# PUMP.net
KiCad netlist of a schematic drawn in Altium Designer
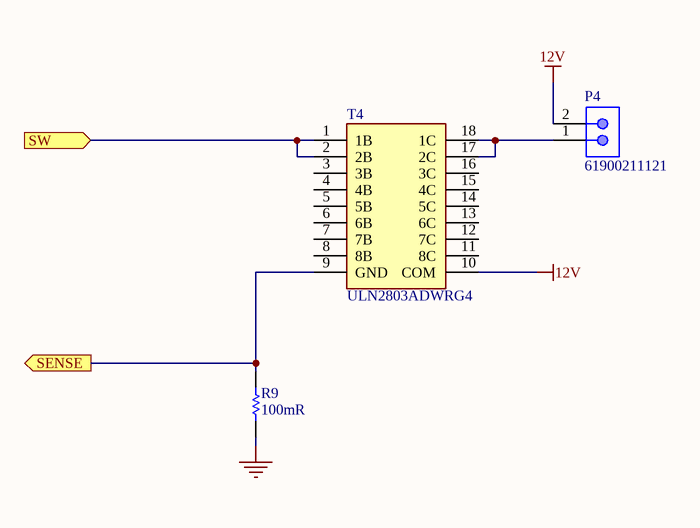
[diagram p0: PUMP.SchDoc]

(export (version "E")
  (design (tool "Eeschema 10.0.6"))
  (components
    (comp (ref "P4")
      (value "61900211121")
      (footprint "61900211121")
      (description "WR-WTB THT Male Vertical Locking Header, pitch 2.54mm, 2p")
      (fields (field (name "PUBLISHER") "Wurth Elektronik"))
      (libsource (lib "Altium_WR-WTB (rev20a)") (part "61900211121"))
    )
    (comp (ref "R9")
      (value "100mR")
      (footprint "RES_1206_H060 (_IPC_MD)")
      (description "100mR 1% 0,25W 200V 1206")
      (fields (field (name "PART NUMBER") "RES100mR1%1206"))
      (libsource (lib "MUAB_Altium_Lib") (part "RES"))
    )
    (comp (ref "T4")
      (value "ULN2803ADWRG4")
      (footprint "OpenBrewie:SOIC127P1030X265-18N")
      (description "Darlington")
      (fields (field (name "MOUSER PART NUMBER") "595-ULN2803ADWRG4"))
      (libsource (lib "OpenBrewie") (part "ULN2803ADWRG4"))
    )
  )
  (nets
    (net (code "1") (name "/SENSE") (class "Default")
      (node (ref "R9") (pin "2") (pinfunction "2_2") (pintype "passive"))
      (node (ref "T4") (pin "9") (pinfunction "GND_9") (pintype "passive"))
    )
    (net (code "2") (name "/SW") (class "Default")
      (node (ref "T4") (pin "1") (pinfunction "1B_1") (pintype "passive"))
      (node (ref "T4") (pin "2") (pinfunction "2B_2") (pintype "passive"))
    )
    (net (code "3") (name "12V") (class "Default")
      (node (ref "P4") (pin "2") (pinfunction "2_2") (pintype "passive"))
      (node (ref "T4") (pin "10") (pinfunction "COM_10") (pintype "passive"))
    )
    (net (code "4") (name "GND") (class "Default")
      (node (ref "R9") (pin "1") (pinfunction "1_1") (pintype "passive"))
    )
    (net (code "5") (name "Net-(T4-1C)") (class "Default")
      (node (ref "P4") (pin "1") (pinfunction "1_1") (pintype "passive"))
      (node (ref "T4") (pin "17") (pinfunction "2C_17") (pintype "passive"))
      (node (ref "T4") (pin "18") (pinfunction "1C_18") (pintype "passive"))
    )
    (net (code "6") (name "unconnected-(T4-3B-Pad3)") (class "Default")
      (node (ref "T4") (pin "3") (pinfunction "3B_3") (pintype "passive"))
    )
    (net (code "7") (name "unconnected-(T4-3C-Pad16)") (class "Default")
      (node (ref "T4") (pin "16") (pinfunction "3C_16") (pintype "passive"))
    )
    (net (code "8") (name "unconnected-(T4-4B-Pad4)") (class "Default")
      (node (ref "T4") (pin "4") (pinfunction "4B_4") (pintype "passive"))
    )
    (net (code "9") (name "unconnected-(T4-4C-Pad15)") (class "Default")
      (node (ref "T4") (pin "15") (pinfunction "4C_15") (pintype "passive"))
    )
    (net (code "10") (name "unconnected-(T4-5B-Pad5)") (class "Default")
      (node (ref "T4") (pin "5") (pinfunction "5B_5") (pintype "passive"))
    )
    (net (code "11") (name "unconnected-(T4-5C-Pad14)") (class "Default")
      (node (ref "T4") (pin "14") (pinfunction "5C_14") (pintype "passive"))
    )
    (net (code "12") (name "unconnected-(T4-6B-Pad6)") (class "Default")
      (node (ref "T4") (pin "6") (pinfunction "6B_6") (pintype "passive"))
    )
    (net (code "13") (name "unconnected-(T4-6C-Pad13)") (class "Default")
      (node (ref "T4") (pin "13") (pinfunction "6C_13") (pintype "passive"))
    )
    (net (code "14") (name "unconnected-(T4-7B-Pad7)") (class "Default")
      (node (ref "T4") (pin "7") (pinfunction "7B_7") (pintype "passive"))
    )
    (net (code "15") (name "unconnected-(T4-7C-Pad12)") (class "Default")
      (node (ref "T4") (pin "12") (pinfunction "7C_12") (pintype "passive"))
    )
    (net (code "16") (name "unconnected-(T4-8B-Pad8)") (class "Default")
      (node (ref "T4") (pin "8") (pinfunction "8B_8") (pintype "passive"))
    )
    (net (code "17") (name "unconnected-(T4-8C-Pad11)") (class "Default")
      (node (ref "T4") (pin "11") (pinfunction "8C_11") (pintype "passive"))
    )
  )
)
